# YOLOTL.net
KiCad netlist of a schematic drawn in EAGLE
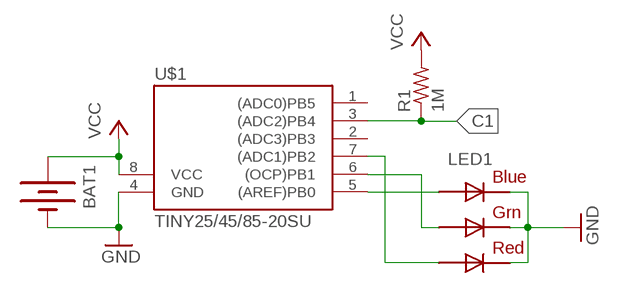
[diagram p0: schematic, sheet 1]

(export (version "E")
  (design (tool "Eeschema 10.0.6"))
  (components
    (comp (ref "BAT1")
      (value "BATTERY20PTH")
      (footprint "eagle-import:BATTCOM_20MM_PTH")
      (libsource (lib "eagle-import") (part "BATTERY20PTH"))
    )
    (comp (ref "LED1")
      (value "RGBLED5050")
      (footprint "eagle-import:RGBLED5050")
      (libsource (lib "eagle-import") (part "RGBLED5050"))
    )
    (comp (ref "R1")
      (value "1M")
      (footprint "eagle-import:R1206")
      (libsource (lib "eagle-import") (part "R-US_R1206"))
    )
    (comp (ref "U$1")
      (value "TINY25/45/85-20SU")
      (footprint "eagle-import:SOIC8")
      (libsource (lib "eagle-import") (part "TINY25/45/85-20SU"))
    )
  )
  (nets
    (net (code "1") (name "C1") (class "Default")
      (node (ref "R1") (pin "1") (pinfunction "1_1") (pintype "passive"))
      (node (ref "U$1") (pin "3") (pinfunction "(ADC2)PB4_3") (pintype "bidirectional"))
    )
    (net (code "2") (name "GND") (class "Default")
      (node (ref "BAT1") (pin "2") (pinfunction "-_2") (pintype "power_in"))
      (node (ref "LED1") (pin "4") (pinfunction "BLUE_C_4") (pintype "bidirectional"))
      (node (ref "LED1") (pin "5") (pinfunction "RED_C_5") (pintype "bidirectional"))
      (node (ref "LED1") (pin "6") (pinfunction "GREEN_C_6") (pintype "bidirectional"))
      (node (ref "U$1") (pin "4") (pinfunction "GND_4") (pintype "power_in"))
    )
    (net (code "3") (name "Net-(LED1-BLUE_A)") (class "Default")
      (node (ref "LED1") (pin "3") (pinfunction "BLUE_A_3") (pintype "bidirectional"))
      (node (ref "U$1") (pin "5") (pinfunction "(AREF)PB0_5") (pintype "bidirectional"))
    )
    (net (code "4") (name "Net-(LED1-GREEN_A)") (class "Default")
      (node (ref "LED1") (pin "1") (pinfunction "GREEN_A_1") (pintype "bidirectional"))
      (node (ref "U$1") (pin "6") (pinfunction "(OCP)PB1_6") (pintype "bidirectional"))
    )
    (net (code "5") (name "Net-(LED1-RED_A)") (class "Default")
      (node (ref "LED1") (pin "2") (pinfunction "RED_A_2") (pintype "bidirectional"))
      (node (ref "U$1") (pin "7") (pinfunction "(ADC1)PB2_7") (pintype "bidirectional"))
    )
    (net (code "6") (name "VCC") (class "Default")
      (node (ref "BAT1") (pin "1") (pinfunction "+_1") (pintype "power_in"))
      (node (ref "R1") (pin "2") (pinfunction "2_2") (pintype "passive"))
      (node (ref "U$1") (pin "8") (pinfunction "VCC_8") (pintype "power_in"))
    )
    (net (code "7") (name "unconnected-(U$1-(ADC0)PB5-Pad1)") (class "Default")
      (node (ref "U$1") (pin "1") (pinfunction "(ADC0)PB5_1") (pintype "bidirectional"))
    )
    (net (code "8") (name "unconnected-(U$1-(ADC3)PB3-Pad2)") (class "Default")
      (node (ref "U$1") (pin "2") (pinfunction "(ADC3)PB3_2") (pintype "bidirectional"))
    )
  )
)
